# Peripherals.net
KiCad netlist of a schematic drawn in Altium Designer
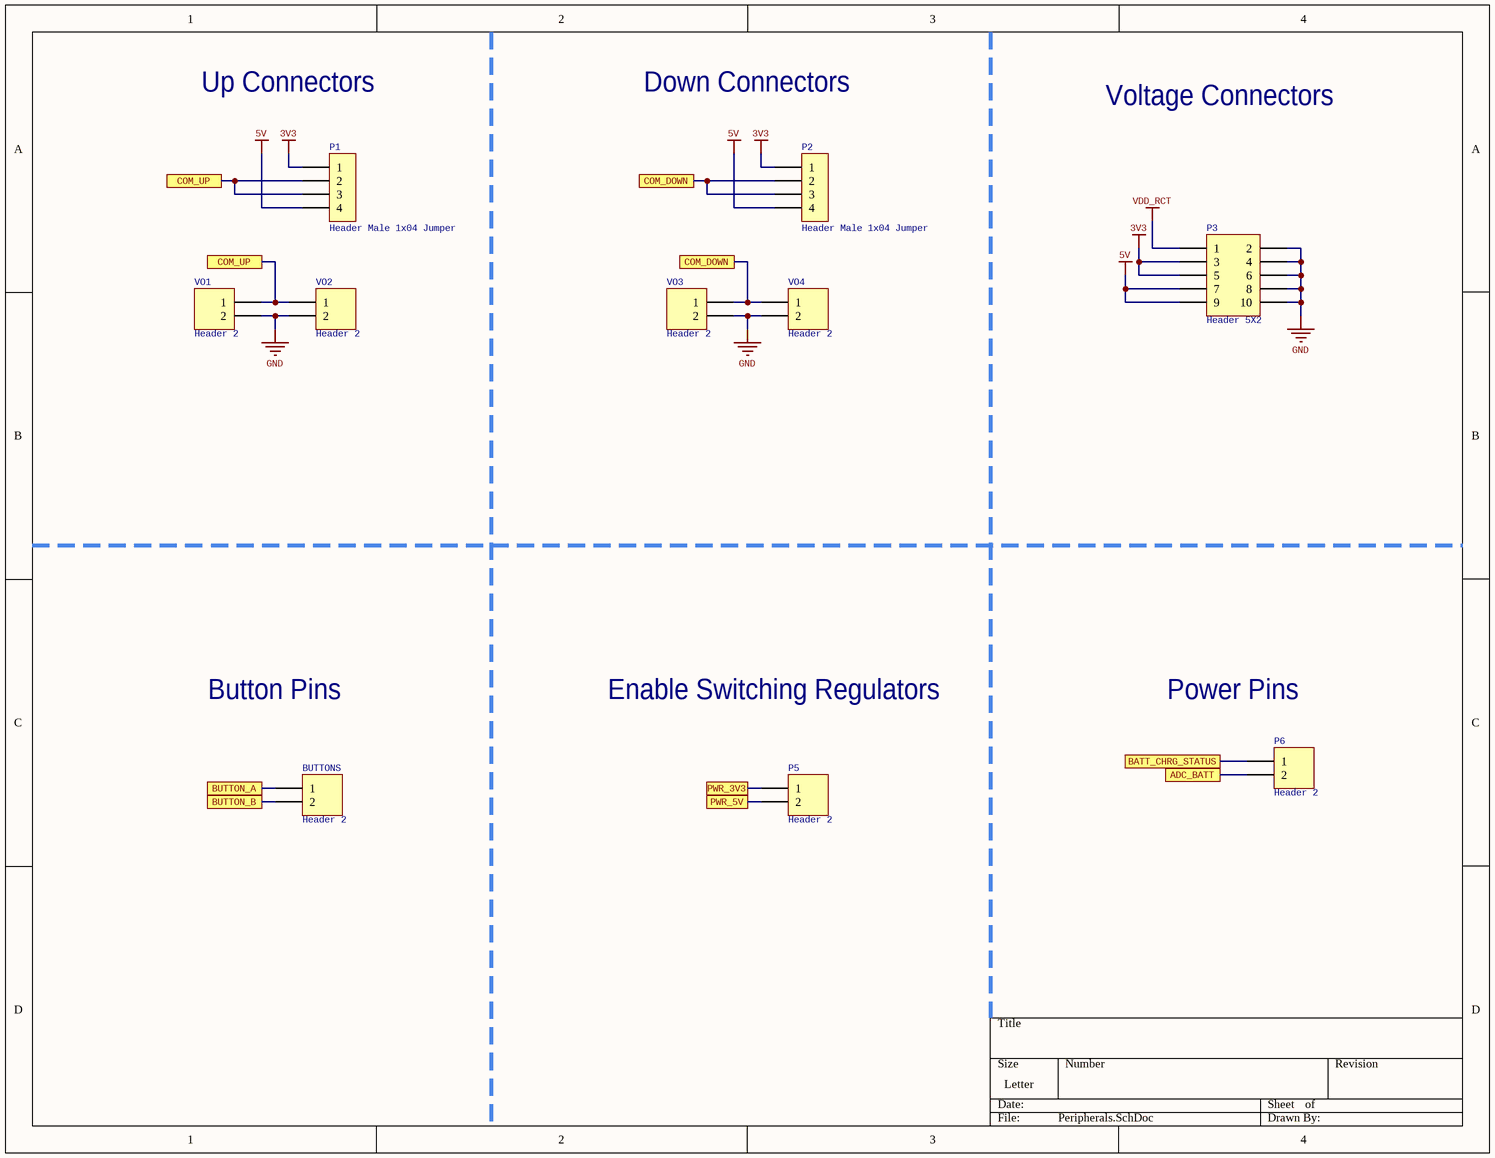
[diagram p0: Peripherals.SchDoc]

(export (version "E")
  (design (tool "Eeschema 10.0.6"))
  (components
    (comp (ref "BUTTONS")
      (value "Header 2")
      (footprint "HDR1X2")
      (description "Header, 2-Pin")
      (fields (field (name "PUBLISHER") "Altium Limited"))
      (libsource (lib "Miscellaneous Connectors") (part "Header 2"))
    )
    (comp (ref "P1")
      (value "Header Male 1x04 Jumper")
      (footprint "Header 1x04 Jumper")
      (description "Header Male Jumper 1x04")
      (libsource (lib "Connectors") (part "Header Male Jumper 1x04"))
    )
    (comp (ref "P2")
      (value "Header Male 1x04 Jumper")
      (footprint "Header 1x04 Jumper")
      (description "Header Male Jumper 1x04")
      (libsource (lib "Connectors") (part "Header Male Jumper 1x04"))
    )
    (comp (ref "P3")
      (value "Header 5X2")
      (footprint "HDR2X5")
      (description "Header, 5-Pin, Dual row")
      (fields (field (name "PUBLISHER") "Altium Limited"))
      (libsource (lib "Miscellaneous Connectors") (part "Header 5X2"))
    )
    (comp (ref "P5")
      (value "Header 2")
      (footprint "HDR1X2")
      (description "Header, 2-Pin")
      (fields (field (name "PUBLISHER") "Altium Limited"))
      (libsource (lib "Miscellaneous Connectors") (part "Header 2"))
    )
    (comp (ref "P6")
      (value "Header 2")
      (footprint "HDR1X2")
      (description "Header, 2-Pin")
      (fields (field (name "PUBLISHER") "Altium Limited"))
      (libsource (lib "Miscellaneous Connectors") (part "Header 2"))
    )
    (comp (ref "VO1")
      (value "Header 2")
      (footprint "HDR1X2")
      (description "Header, 2-Pin")
      (fields (field (name "PUBLISHER") "Altium Limited"))
      (libsource (lib "") (part "Header 2_1"))
    )
    (comp (ref "VO2")
      (value "Header 2")
      (footprint "HDR1X2")
      (description "Header, 2-Pin")
      (fields (field (name "PUBLISHER") "Altium Limited"))
      (libsource (lib "Miscellaneous Connectors") (part "Header 2"))
    )
    (comp (ref "VO3")
      (value "Header 2")
      (footprint "HDR1X2")
      (description "Header, 2-Pin")
      (fields (field (name "PUBLISHER") "Altium Limited"))
      (libsource (lib "") (part "Header 2_1"))
    )
    (comp (ref "VO4")
      (value "Header 2")
      (footprint "HDR1X2")
      (description "Header, 2-Pin")
      (fields (field (name "PUBLISHER") "Altium Limited"))
      (libsource (lib "Miscellaneous Connectors") (part "Header 2"))
    )
  )
  (nets
    (net (code "1") (name "/ADC_BATT") (class "Default")
      (node (ref "P6") (pin "2") (pinfunction "2_2") (pintype "passive"))
    )
    (net (code "2") (name "/BATT_CHRG_STATUS") (class "Default")
      (node (ref "P6") (pin "1") (pinfunction "1_1") (pintype "passive"))
    )
    (net (code "3") (name "/BUTTON_A") (class "Default")
      (node (ref "BUTTONS") (pin "1") (pinfunction "1_1") (pintype "passive"))
    )
    (net (code "4") (name "/BUTTON_B") (class "Default")
      (node (ref "BUTTONS") (pin "2") (pinfunction "2_2") (pintype "passive"))
    )
    (net (code "5") (name "/COM_DOWN") (class "Default")
      (node (ref "P2") (pin "2") (pinfunction "2_2") (pintype "passive"))
      (node (ref "P2") (pin "3") (pinfunction "3_3") (pintype "passive"))
      (node (ref "VO3") (pin "1") (pinfunction "1_1") (pintype "passive"))
      (node (ref "VO4") (pin "1") (pinfunction "1_1") (pintype "passive"))
    )
    (net (code "6") (name "/COM_UP") (class "Default")
      (node (ref "P1") (pin "2") (pinfunction "2_2") (pintype "passive"))
      (node (ref "P1") (pin "3") (pinfunction "3_3") (pintype "passive"))
      (node (ref "VO1") (pin "1") (pinfunction "1_1") (pintype "passive"))
      (node (ref "VO2") (pin "1") (pinfunction "1_1") (pintype "passive"))
    )
    (net (code "7") (name "/PWR_3V3") (class "Default")
      (node (ref "P5") (pin "1") (pinfunction "1_1") (pintype "passive"))
    )
    (net (code "8") (name "/PWR_5V") (class "Default")
      (node (ref "P5") (pin "2") (pinfunction "2_2") (pintype "passive"))
    )
    (net (code "9") (name "3V3") (class "Default")
      (node (ref "P1") (pin "1") (pinfunction "1_1") (pintype "passive"))
      (node (ref "P2") (pin "1") (pinfunction "1_1") (pintype "passive"))
      (node (ref "P3") (pin "3") (pinfunction "3_3") (pintype "passive"))
      (node (ref "P3") (pin "5") (pinfunction "5_5") (pintype "passive"))
    )
    (net (code "10") (name "5V") (class "Default")
      (node (ref "P1") (pin "4") (pinfunction "4_4") (pintype "passive"))
      (node (ref "P2") (pin "4") (pinfunction "4_4") (pintype "passive"))
      (node (ref "P3") (pin "7") (pinfunction "7_7") (pintype "passive"))
      (node (ref "P3") (pin "9") (pinfunction "9_9") (pintype "passive"))
    )
    (net (code "11") (name "GND") (class "Default")
      (node (ref "P3") (pin "10") (pinfunction "10_10") (pintype "passive"))
      (node (ref "P3") (pin "2") (pinfunction "2_2") (pintype "passive"))
      (node (ref "P3") (pin "4") (pinfunction "4_4") (pintype "passive"))
      (node (ref "P3") (pin "6") (pinfunction "6_6") (pintype "passive"))
      (node (ref "P3") (pin "8") (pinfunction "8_8") (pintype "passive"))
      (node (ref "VO1") (pin "2") (pinfunction "2_2") (pintype "passive"))
      (node (ref "VO2") (pin "2") (pinfunction "2_2") (pintype "passive"))
      (node (ref "VO3") (pin "2") (pinfunction "2_2") (pintype "passive"))
      (node (ref "VO4") (pin "2") (pinfunction "2_2") (pintype "passive"))
    )
    (net (code "12") (name "VDD_RCT") (class "Default")
      (node (ref "P3") (pin "1") (pinfunction "1_1") (pintype "passive"))
    )
  )
)
